# Esquematico.net
KiCad netlist of a schematic drawn in Altium Designer
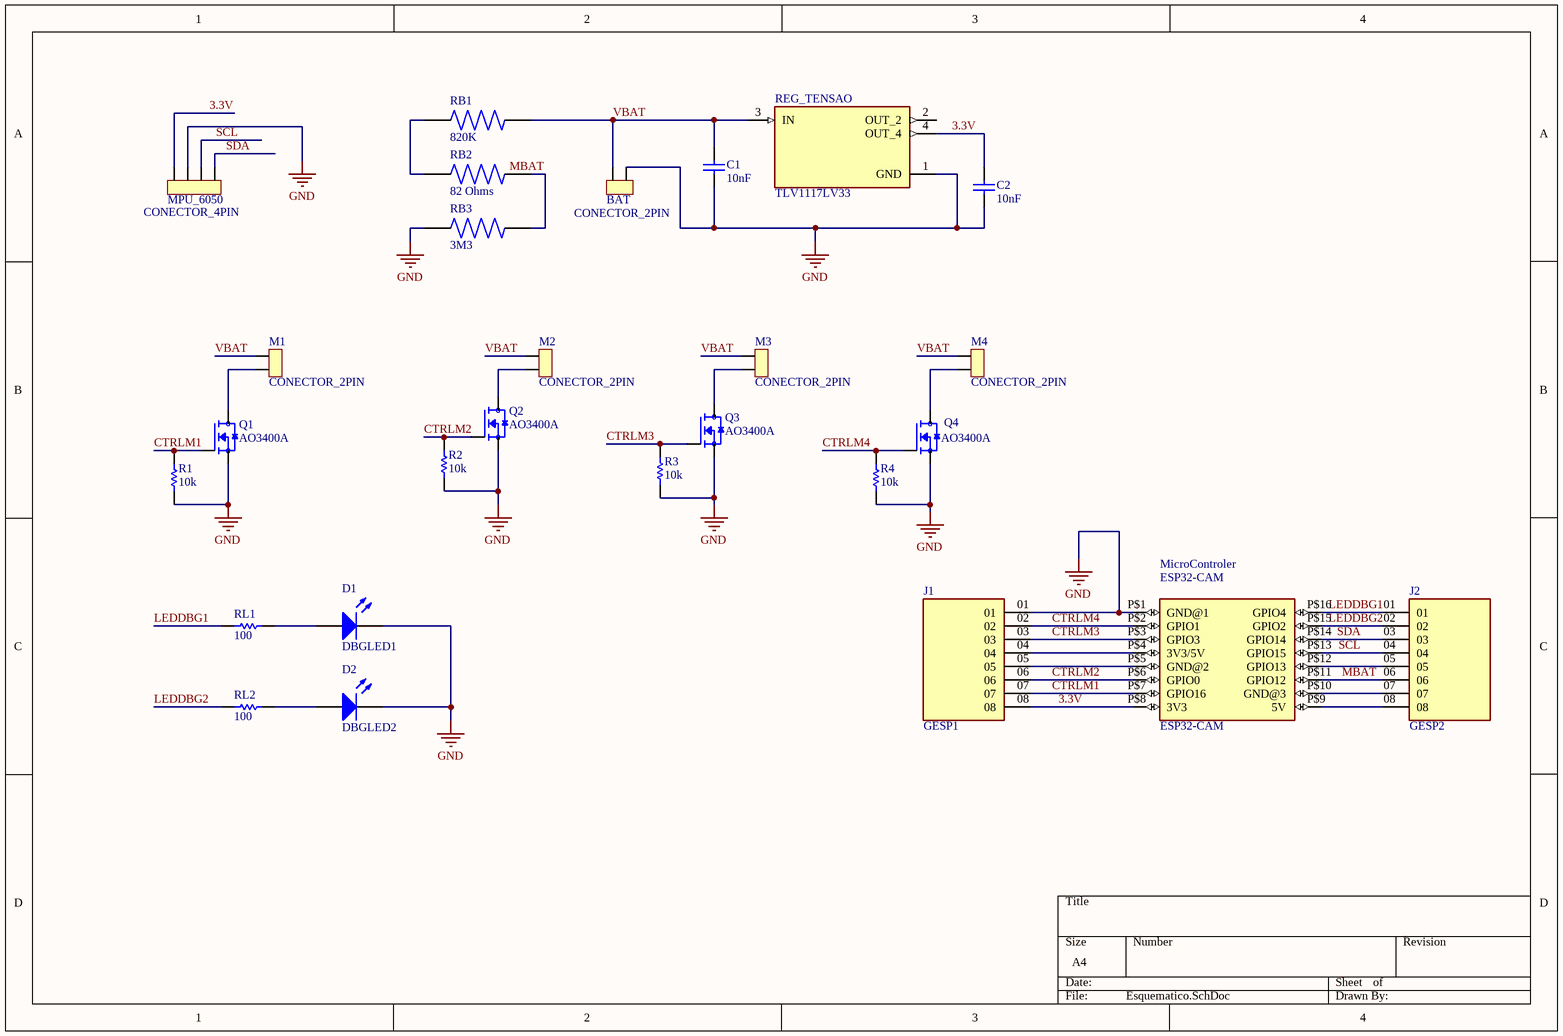
[diagram p0: Esquematico.SchDoc]

(export (version "E")
  (design (tool "Eeschema 10.0.6"))
  (components
    (comp (ref "BAT")
      (value "CONECTOR_2PIN")
      (footprint "CON2")
      (libsource (lib "") (part "CONECTOR_2PIN_1"))
    )
    (comp (ref "C1")
      (value "CAP")
      (footprint "CAP 0805")
      (description "Capacitor")
      (fields (field (name "VALOR") "10nF"))
      (libsource (lib "Biblioteca Trincabotz") (part "CAP. CERÂMICO"))
    )
    (comp (ref "C2")
      (value "CAP")
      (footprint "CAP 0805")
      (description "Capacitor")
      (fields (field (name "VALOR") "10nF"))
      (libsource (lib "Biblioteca Trincabotz") (part "CAP. CERÂMICO"))
    )
    (comp (ref "D1")
      (value "DBGLED1")
      (footprint "LED 0805")
      (libsource (lib "Biblioteca Trincabotz (1)") (part "LED"))
    )
    (comp (ref "D2")
      (value "DBGLED2")
      (footprint "LED 0805")
      (libsource (lib "Biblioteca Trincabotz (1)") (part "LED"))
    )
    (comp (ref "J1")
      (value "GESP1")
      (footprint "SAMTEC_SS-108-T-2")
      (description "SS Series .100 Single Row Screw Machine Socket Strip")
      (fields (field (name "MP") "SS-108-T-2") (field (name "MF") "Samtec"))
      (libsource (lib "8PIN-CONECTOR") (part "SS-108-T-2"))
    )
    (comp (ref "J2")
      (value "GESP2")
      (footprint "SAMTEC_SS-108-T-2")
      (description "SS Series .100 Single Row Screw Machine Socket Strip")
      (fields (field (name "MP") "SS-108-T-2") (field (name "MF") "Samtec"))
      (libsource (lib "") (part "SS-108-T-2_1"))
    )
    (comp (ref "M1")
      (value "CONECTOR_2PIN")
      (footprint "CON2")
      (libsource (lib "Biblioteca Trincabotz") (part "CONECTOR_2PIN"))
    )
    (comp (ref "M2")
      (value "CONECTOR_2PIN")
      (footprint "CON2")
      (libsource (lib "Biblioteca Trincabotz") (part "CONECTOR_2PIN"))
    )
    (comp (ref "M3")
      (value "CONECTOR_2PIN")
      (footprint "CON2")
      (libsource (lib "Biblioteca Trincabotz") (part "CONECTOR_2PIN"))
    )
    (comp (ref "M4")
      (value "CONECTOR_2PIN")
      (footprint "CON2")
      (libsource (lib "Biblioteca Trincabotz") (part "CONECTOR_2PIN"))
    )
    (comp (ref "MicroControler")
      (value "ESP32-CAM")
      (footprint "ESP32-CAM")
      (fields (field (name "MF") "AI-Thinker"))
      (libsource (lib "ESP32_CAM") (part "ESP32-CAM"))
    )
    (comp (ref "MPU_6050")
      (value "CONECTOR_4PIN")
      (footprint "CON4")
      (libsource (lib "Biblioteca Trincabotz") (part "CONECTOR_4PIN"))
    )
    (comp (ref "Q1")
      (value "AO3400A")
      (footprint "SOT95P280X125-3N")
      (description "N-Channel 30 V 5.7A (Ta) 1.4W (Ta) Surface Mount SOT-23-3")
      (fields (field (name "MF") "Alpha & Omega Semiconductor"))
      (libsource (lib "MOSFETAO3400A") (part "AO3400A"))
    )
    (comp (ref "Q2")
      (value "AO3400A")
      (footprint "SOT95P280X125-3N")
      (description "N-Channel 30 V 5.7A (Ta) 1.4W (Ta) Surface Mount SOT-23-3")
      (fields (field (name "MF") "Alpha & Omega Semiconductor"))
      (libsource (lib "MOSFETAO3400A") (part "AO3400A"))
    )
    (comp (ref "Q3")
      (value "AO3400A")
      (footprint "SOT95P280X125-3N")
      (description "N-Channel 30 V 5.7A (Ta) 1.4W (Ta) Surface Mount SOT-23-3")
      (fields (field (name "MF") "Alpha & Omega Semiconductor"))
      (libsource (lib "MOSFETAO3400A") (part "AO3400A"))
    )
    (comp (ref "Q4")
      (value "AO3400A")
      (footprint "SOT95P280X125-3N")
      (description "N-Channel 30 V 5.7A (Ta) 1.4W (Ta) Surface Mount SOT-23-3")
      (fields (field (name "MF") "Alpha & Omega Semiconductor"))
      (libsource (lib "MOSFETAO3400A") (part "AO3400A"))
    )
    (comp (ref "R1")
      (value "10k")
      (footprint "RES 0805")
      (description "Resistor")
      (fields (field (name "Comment") "RESISTOR"))
      (libsource (lib "Biblioteca Trincabotz") (part "RESISTOR"))
    )
    (comp (ref "R2")
      (value "10k")
      (footprint "RES 0805")
      (description "Resistor")
      (fields (field (name "Comment") "RESISTOR"))
      (libsource (lib "Biblioteca Trincabotz") (part "RESISTOR"))
    )
    (comp (ref "R3")
      (value "10k")
      (footprint "RES 0805")
      (description "Resistor")
      (fields (field (name "Comment") "RESISTOR"))
      (libsource (lib "Biblioteca Trincabotz") (part "RESISTOR"))
    )
    (comp (ref "R4")
      (value "10k")
      (footprint "RES 0805")
      (description "Resistor")
      (fields (field (name "Comment") "RESISTOR"))
      (libsource (lib "Biblioteca Trincabotz") (part "RESISTOR"))
    )
    (comp (ref "RB1")
      (value "820K")
      (footprint "RESAD700W45L350D185")
      (description "1 MOhms Â±5% 0.25W, 1/4W Through Hole Resistor Axial - Carbon Film")
      (fields (field (name "MF") "TE Connectivity") (field (name "MP") "3-1623927-1"))
      (libsource (lib "ResistorTHL") (part "3-1623927-1"))
    )
    (comp (ref "RB2")
      (value "82 Ohms")
      (footprint "RESAD700W45L350D185")
      (description "1 MOhms Â±5% 0.25W, 1/4W Through Hole Resistor Axial - Carbon Film")
      (fields (field (name "MF") "TE Connectivity") (field (name "MP") "3-1623927-1"))
      (libsource (lib "ResistorTHL") (part "3-1623927-1"))
    )
    (comp (ref "RB3")
      (value "3M3")
      (footprint "RESAD700W45L350D185")
      (description "1 MOhms Â±5% 0.25W, 1/4W Through Hole Resistor Axial - Carbon Film")
      (fields (field (name "MF") "TE Connectivity") (field (name "MP") "3-1623927-1"))
      (libsource (lib "ResistorTHL") (part "3-1623927-1"))
    )
    (comp (ref "REG_TENSAO")
      (value "TLV1117LV33")
      (footprint "VREG_TLV1117LV33DCYR")
      (description "1-A, low-dropout voltage regulator")
      (fields (field (name "MF") "Texas Instruments") (field (name "MP") "TLV1117LV33DCYR"))
      (libsource (lib "REG_TENSAO") (part "TLV1117LV33DCYR"))
    )
    (comp (ref "RL1")
      (value "100")
      (footprint "RES 0805")
      (description "Resistor")
      (fields (field (name "Comment") "RESISTOR"))
      (libsource (lib "Biblioteca Trincabotz (1)") (part "RESISTOR"))
    )
    (comp (ref "RL2")
      (value "100")
      (footprint "RES 0805")
      (description "Resistor")
      (fields (field (name "Comment") "RESISTOR"))
      (libsource (lib "Biblioteca Trincabotz (1)") (part "RESISTOR"))
    )
  )
  (nets
    (net (code "1") (name "/3.3V") (class "Default")
      (node (ref "C2") (pin "2") (pinfunction "2_2") (pintype "passive"))
      (node (ref "J1") (pin "08") (pinfunction "08_08") (pintype "passive"))
      (node (ref "MPU_6050") (pin "1") (pinfunction "1_1") (pintype "passive"))
      (node (ref "MicroControler") (pin "P$8") (pinfunction "3V3_P$8") (pintype "bidirectional"))
      (node (ref "REG_TENSAO") (pin "4") (pinfunction "OUT_4_4") (pintype "output"))
    )
    (net (code "2") (name "/CTRLM1") (class "Default")
      (node (ref "J1") (pin "07") (pinfunction "07_07") (pintype "passive"))
      (node (ref "MicroControler") (pin "P$7") (pinfunction "GPIO16_P$7") (pintype "bidirectional"))
      (node (ref "Q1") (pin "1") (pinfunction "G_1") (pintype "passive"))
      (node (ref "R1") (pin "2") (pinfunction "2_2") (pintype "passive"))
    )
    (net (code "3") (name "/CTRLM2") (class "Default")
      (node (ref "J1") (pin "06") (pinfunction "06_06") (pintype "passive"))
      (node (ref "MicroControler") (pin "P$6") (pinfunction "GPIO0_P$6") (pintype "bidirectional"))
      (node (ref "Q2") (pin "1") (pinfunction "G_1") (pintype "passive"))
      (node (ref "R2") (pin "2") (pinfunction "2_2") (pintype "passive"))
    )
    (net (code "4") (name "/CTRLM3") (class "Default")
      (node (ref "J1") (pin "03") (pinfunction "03_03") (pintype "passive"))
      (node (ref "MicroControler") (pin "P$3") (pinfunction "GPIO3_P$3") (pintype "bidirectional"))
      (node (ref "Q3") (pin "1") (pinfunction "G_1") (pintype "passive"))
      (node (ref "R3") (pin "2") (pinfunction "2_2") (pintype "passive"))
    )
    (net (code "5") (name "/CTRLM4") (class "Default")
      (node (ref "J1") (pin "02") (pinfunction "02_02") (pintype "passive"))
      (node (ref "MicroControler") (pin "P$2") (pinfunction "GPIO1_P$2") (pintype "bidirectional"))
      (node (ref "Q4") (pin "1") (pinfunction "G_1") (pintype "passive"))
      (node (ref "R4") (pin "2") (pinfunction "2_2") (pintype "passive"))
    )
    (net (code "6") (name "/LEDDBG1") (class "Default")
      (node (ref "J2") (pin "01") (pinfunction "01_01") (pintype "passive"))
      (node (ref "MicroControler") (pin "P$16") (pinfunction "GPIO4_P$16") (pintype "bidirectional"))
      (node (ref "RL1") (pin "1") (pinfunction "1_1") (pintype "passive"))
    )
    (net (code "7") (name "/LEDDBG2") (class "Default")
      (node (ref "J2") (pin "02") (pinfunction "02_02") (pintype "passive"))
      (node (ref "MicroControler") (pin "P$15") (pinfunction "GPIO2_P$15") (pintype "bidirectional"))
      (node (ref "RL2") (pin "1") (pinfunction "1_1") (pintype "passive"))
    )
    (net (code "8") (name "/MBAT") (class "Default")
      (node (ref "J2") (pin "06") (pinfunction "06_06") (pintype "passive"))
      (node (ref "MicroControler") (pin "P$11") (pinfunction "GPIO12_P$11") (pintype "bidirectional"))
      (node (ref "RB2") (pin "2") (pinfunction "2_2") (pintype "passive"))
      (node (ref "RB3") (pin "2") (pinfunction "2_2") (pintype "passive"))
    )
    (net (code "9") (name "/SCL") (class "Default")
      (node (ref "J2") (pin "04") (pinfunction "04_04") (pintype "passive"))
      (node (ref "MPU_6050") (pin "3") (pinfunction "3_3") (pintype "passive"))
      (node (ref "MicroControler") (pin "P$13") (pinfunction "GPIO15_P$13") (pintype "bidirectional"))
    )
    (net (code "10") (name "/SDA") (class "Default")
      (node (ref "J2") (pin "03") (pinfunction "03_03") (pintype "passive"))
      (node (ref "MPU_6050") (pin "4") (pinfunction "4_4") (pintype "passive"))
      (node (ref "MicroControler") (pin "P$14") (pinfunction "GPIO14_P$14") (pintype "bidirectional"))
    )
    (net (code "11") (name "/VBAT") (class "Default")
      (node (ref "BAT") (pin "1") (pinfunction "1_1") (pintype "passive"))
      (node (ref "C1") (pin "2") (pinfunction "2_2") (pintype "passive"))
      (node (ref "M1") (pin "2") (pinfunction "2_2") (pintype "passive"))
      (node (ref "M2") (pin "2") (pinfunction "2_2") (pintype "passive"))
      (node (ref "M3") (pin "2") (pinfunction "2_2") (pintype "passive"))
      (node (ref "M4") (pin "2") (pinfunction "2_2") (pintype "passive"))
      (node (ref "RB1") (pin "2") (pinfunction "2_2") (pintype "passive"))
      (node (ref "REG_TENSAO") (pin "3") (pinfunction "IN_3") (pintype "input"))
    )
    (net (code "12") (name "GND") (class "Default")
      (node (ref "BAT") (pin "2") (pinfunction "2_2") (pintype "passive"))
      (node (ref "C1") (pin "1") (pinfunction "1_1") (pintype "passive"))
      (node (ref "C2") (pin "1") (pinfunction "1_1") (pintype "passive"))
      (node (ref "D1") (pin "2") (pinfunction "K_2") (pintype "passive"))
      (node (ref "D2") (pin "2") (pinfunction "K_2") (pintype "passive"))
      (node (ref "J1") (pin "01") (pinfunction "01_01") (pintype "passive"))
      (node (ref "MPU_6050") (pin "2") (pinfunction "2_2") (pintype "passive"))
      (node (ref "MicroControler") (pin "P$1") (pinfunction "GND@1_P$1") (pintype "bidirectional"))
      (node (ref "Q1") (pin "2") (pinfunction "S_2") (pintype "passive"))
      (node (ref "Q2") (pin "2") (pinfunction "S_2") (pintype "passive"))
      (node (ref "Q3") (pin "2") (pinfunction "S_2") (pintype "passive"))
      (node (ref "Q4") (pin "2") (pinfunction "S_2") (pintype "passive"))
      (node (ref "R1") (pin "1") (pinfunction "1_1") (pintype "passive"))
      (node (ref "R2") (pin "1") (pinfunction "1_1") (pintype "passive"))
      (node (ref "R3") (pin "1") (pinfunction "1_1") (pintype "passive"))
      (node (ref "R4") (pin "1") (pinfunction "1_1") (pintype "passive"))
      (node (ref "RB3") (pin "1") (pinfunction "1_1") (pintype "passive"))
      (node (ref "REG_TENSAO") (pin "1") (pinfunction "GND_1") (pintype "power_in"))
    )
    (net (code "13") (name "Net-(D1-A)") (class "Default")
      (node (ref "D1") (pin "1") (pinfunction "A_1") (pintype "passive"))
      (node (ref "RL1") (pin "2") (pinfunction "2_2") (pintype "passive"))
    )
    (net (code "14") (name "Net-(D2-A)") (class "Default")
      (node (ref "D2") (pin "1") (pinfunction "A_1") (pintype "passive"))
      (node (ref "RL2") (pin "2") (pinfunction "2_2") (pintype "passive"))
    )
    (net (code "15") (name "Net-(MicroControler-3V3{slash}5V)") (class "Default")
      (node (ref "J1") (pin "04") (pinfunction "04_04") (pintype "passive"))
      (node (ref "MicroControler") (pin "P$4") (pinfunction "3V3/5V_P$4") (pintype "bidirectional"))
    )
    (net (code "16") (name "Net-(MicroControler-5V)") (class "Default")
      (node (ref "J2") (pin "08") (pinfunction "08_08") (pintype "passive"))
      (node (ref "MicroControler") (pin "P$9") (pinfunction "5V_P$9") (pintype "bidirectional"))
    )
    (net (code "17") (name "Net-(MicroControler-GND@2)") (class "Default")
      (node (ref "J1") (pin "05") (pinfunction "05_05") (pintype "passive"))
      (node (ref "MicroControler") (pin "P$5") (pinfunction "GND@2_P$5") (pintype "bidirectional"))
    )
    (net (code "18") (name "Net-(MicroControler-GND@3)") (class "Default")
      (node (ref "J2") (pin "07") (pinfunction "07_07") (pintype "passive"))
      (node (ref "MicroControler") (pin "P$10") (pinfunction "GND@3_P$10") (pintype "bidirectional"))
    )
    (net (code "19") (name "Net-(MicroControler-GPIO13)") (class "Default")
      (node (ref "J2") (pin "05") (pinfunction "05_05") (pintype "passive"))
      (node (ref "MicroControler") (pin "P$12") (pinfunction "GPIO13_P$12") (pintype "bidirectional"))
    )
    (net (code "20") (name "Net-(Q1-D)") (class "Default")
      (node (ref "M1") (pin "1") (pinfunction "1_1") (pintype "passive"))
      (node (ref "Q1") (pin "3") (pinfunction "D_3") (pintype "passive"))
    )
    (net (code "21") (name "Net-(Q2-D)") (class "Default")
      (node (ref "M2") (pin "1") (pinfunction "1_1") (pintype "passive"))
      (node (ref "Q2") (pin "3") (pinfunction "D_3") (pintype "passive"))
    )
    (net (code "22") (name "Net-(Q3-D)") (class "Default")
      (node (ref "M3") (pin "1") (pinfunction "1_1") (pintype "passive"))
      (node (ref "Q3") (pin "3") (pinfunction "D_3") (pintype "passive"))
    )
    (net (code "23") (name "Net-(Q4-D)") (class "Default")
      (node (ref "M4") (pin "1") (pinfunction "1_1") (pintype "passive"))
      (node (ref "Q4") (pin "3") (pinfunction "D_3") (pintype "passive"))
    )
    (net (code "24") (name "Net-(RB1-Pad1)") (class "Default")
      (node (ref "RB1") (pin "1") (pinfunction "1_1") (pintype "passive"))
      (node (ref "RB2") (pin "1") (pinfunction "1_1") (pintype "passive"))
    )
    (net (code "25") (name "unconnected-(REG_TENSAO-OUT_2-Pad2)") (class "Default")
      (node (ref "REG_TENSAO") (pin "2") (pinfunction "OUT_2_2") (pintype "output"))
    )
  )
)
